# Module_MCU_ESP32Embed.net
KiCad netlist of a schematic drawn in EAGLE
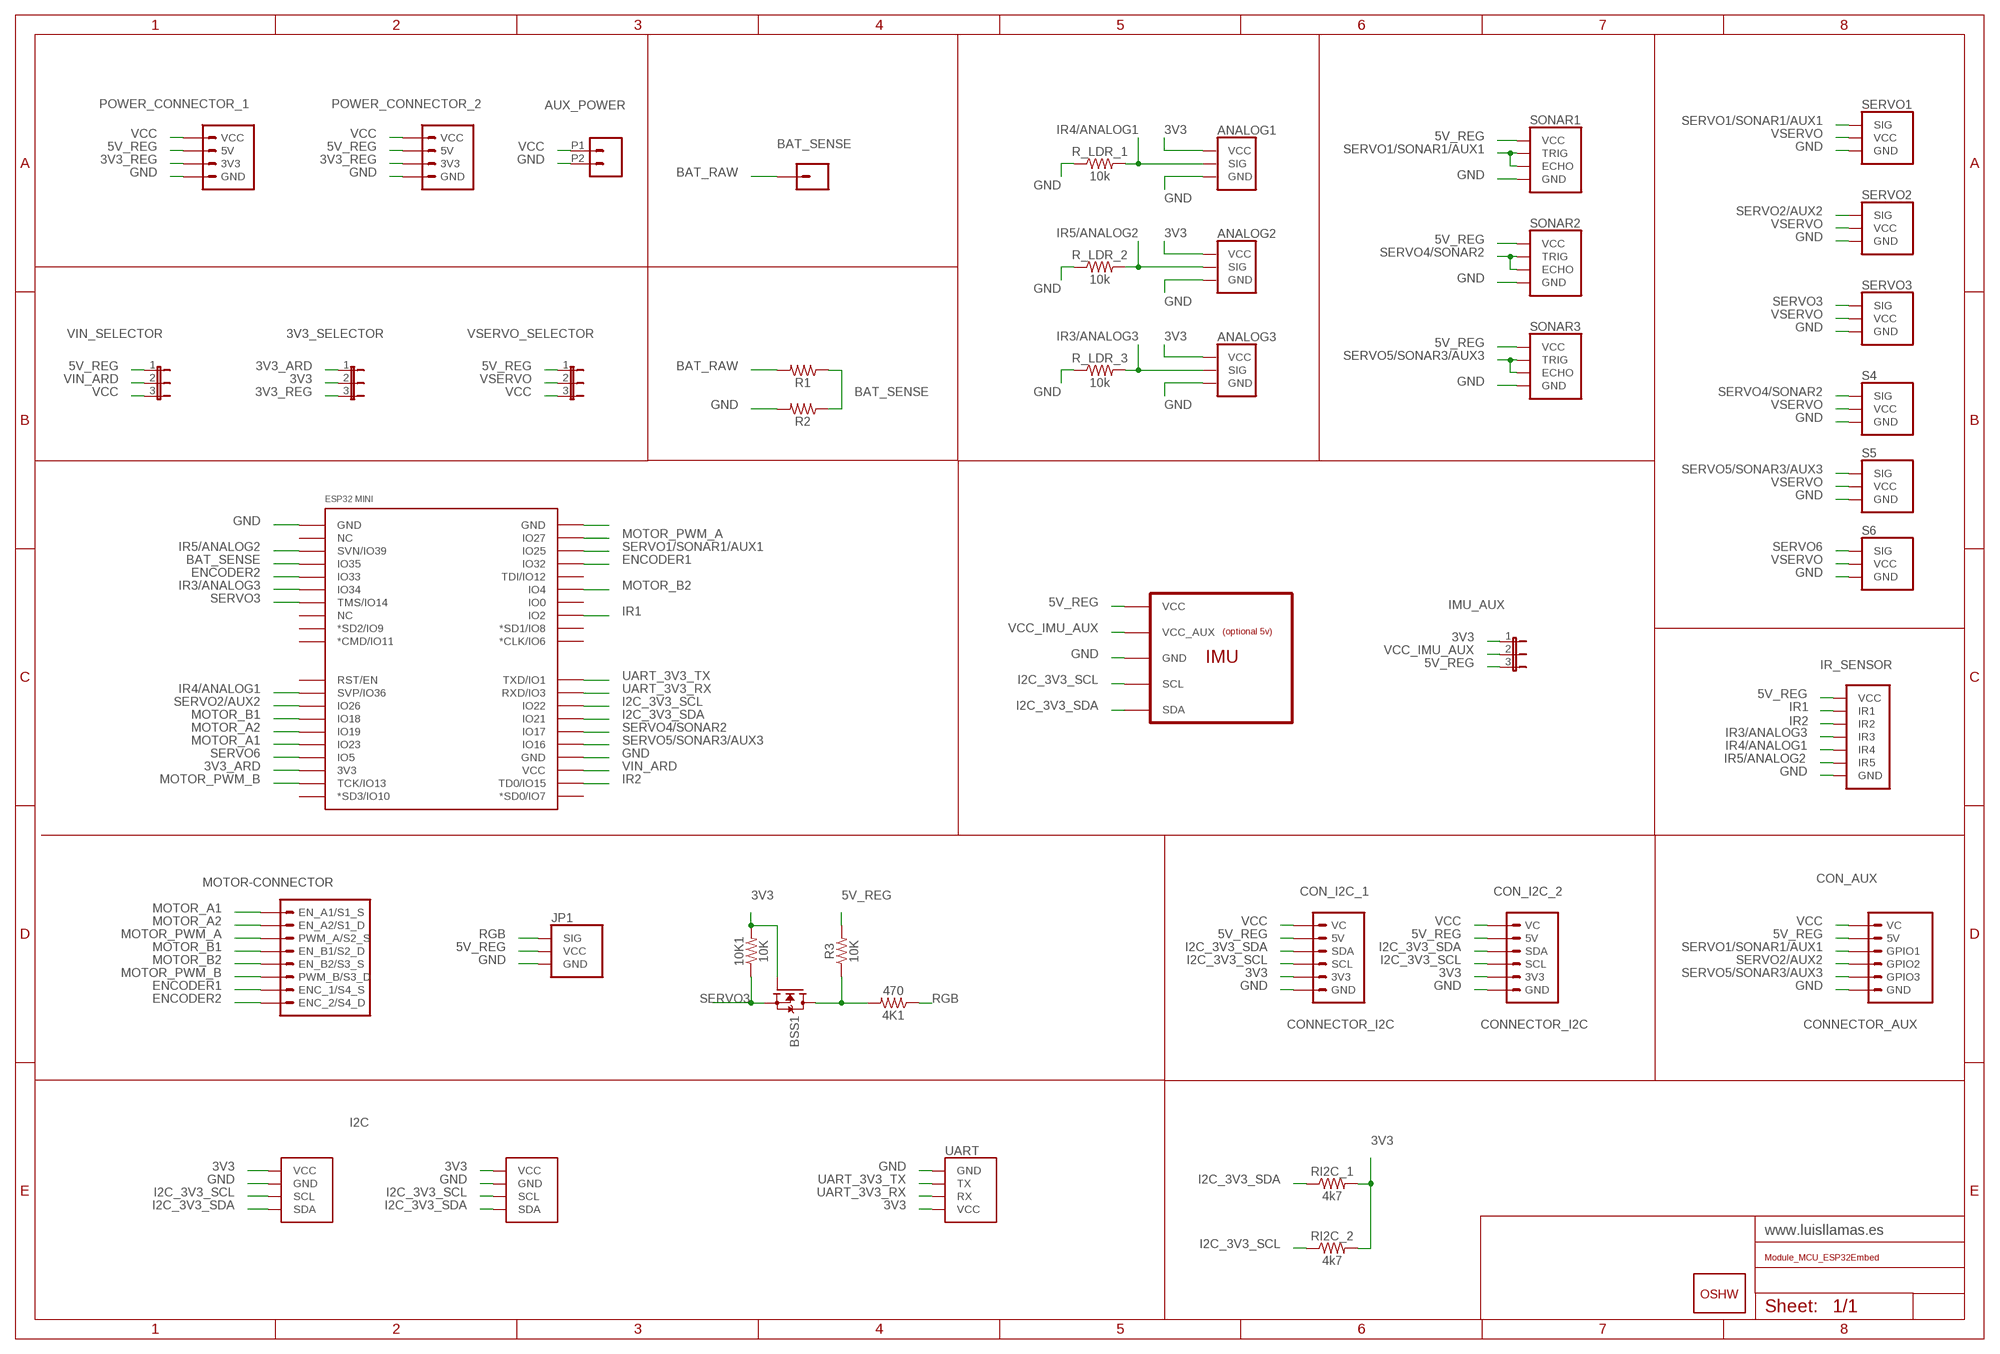
[diagram p0: schematic, sheet 1]

(export (version "E")
  (design (tool "Eeschema 10.0.6"))
  (components
    (comp (ref "3V3_SELECTOR")
      (value "JUMPER_3")
      (footprint "eagle-import:JUMPER_3")
      (libsource (lib "eagle-import") (part "JUMPER_3"))
    )
    (comp (ref "4K1")
      (value "470")
      (footprint "eagle-import:0805")
      (libsource (lib "eagle-import") (part "RESISTOR0805"))
    )
    (comp (ref "10K1")
      (value "10K")
      (footprint "eagle-import:0805")
      (libsource (lib "eagle-import") (part "RESISTOR0805"))
    )
    (comp (ref "ANALOG1")
      (value "LDR/OCT")
      (footprint "eagle-import:LDR")
      (libsource (lib "eagle-import") (part "LDR/OCT"))
    )
    (comp (ref "ANALOG2")
      (value "LDR/OCT")
      (footprint "eagle-import:LDR")
      (libsource (lib "eagle-import") (part "LDR/OCT"))
    )
    (comp (ref "ANALOG3")
      (value "LDR/OCT")
      (footprint "eagle-import:LDR")
      (libsource (lib "eagle-import") (part "LDR/OCT"))
    )
    (comp (ref "AUX_POWER")
      (value "CONN_022.54MM_SCREWTERM")
      (footprint "eagle-import:1X02_2.54_SCREWTERM")
      (libsource (lib "eagle-import") (part "CONN_022.54MM_SCREWTERM"))
    )
    (comp (ref "BAT_SENSE")
      (value "CONN_01")
      (footprint "eagle-import:1X01")
      (libsource (lib "eagle-import") (part "CONN_01"))
    )
    (comp (ref "BSS1")
      (value "MOSFET-N-SOT23")
      (footprint "eagle-import:SOT23")
      (libsource (lib "eagle-import") (part "MOSFET-N-SOT23"))
    )
    (comp (ref "CON_AUX")
      (value "CONNECTOR_AUX")
      (footprint "eagle-import:CONNECTOR_AUX")
      (libsource (lib "eagle-import") (part "CONNECTOR_AUX"))
    )
    (comp (ref "CON_I2C_1")
      (value "CONNECTOR_I2C")
      (footprint "eagle-import:CONNECTOR_I2C")
      (libsource (lib "eagle-import") (part "CONNECTOR_I2C"))
    )
    (comp (ref "CON_I2C_2")
      (value "CONNECTOR_I2C")
      (footprint "eagle-import:CONNECTOR_I2C")
      (libsource (lib "eagle-import") (part "CONNECTOR_I2C"))
    )
    (comp (ref "GOLD_ORB_SM1")
      (value "OSHWLOGO_GOLD_ORB_MED")
      (footprint "eagle-import:OSHW1")
      (libsource (lib "eagle-import") (part "OSHWLOGO_GOLD_ORB_MED"))
    )
    (comp (ref "I2C_1")
      (value "I2C")
      (footprint "eagle-import:I2C_VCC_GND_SCL_SDA")
      (libsource (lib "eagle-import") (part "GENERIC_I2CVCC_GND_SCL_SDA"))
    )
    (comp (ref "I2C_2")
      (value "GENERIC_I2CVCC_GND_SCL_SDA")
      (footprint "eagle-import:I2C_VCC_GND_SCL_SDA")
      (libsource (lib "eagle-import") (part "GENERIC_I2CVCC_GND_SCL_SDA"))
    )
    (comp (ref "IMU_AUX")
      (value "JUMPER_3")
      (footprint "eagle-import:JUMPER_3")
      (libsource (lib "eagle-import") (part "JUMPER_3"))
    )
    (comp (ref "IR_SENSOR")
      (value "IR-5/OCT")
      (footprint "eagle-import:IR-5")
      (libsource (lib "eagle-import") (part "IR-5/OCT"))
    )
    (comp (ref "JP1")
      (value "SERVOSERVO")
      (footprint "eagle-import:SERVO")
      (libsource (lib "eagle-import") (part "SERVOSERVO"))
    )
    (comp (ref "MOTOR_CONNECTOR")
      (value "MOTOR-CONNECTOR")
      (footprint "eagle-import:MOTOR-CONNECTOR")
      (libsource (lib "eagle-import") (part "MOTOR-CONNECTOR"))
    )
    (comp (ref "POWER_CONNECTOR_1")
      (value "POWER-CONNECTOR")
      (footprint "eagle-import:POWER-CONNECTOR")
      (libsource (lib "eagle-import") (part "POWER-CONNECTOR"))
    )
    (comp (ref "POWER_CONNECTOR_2")
      (value "POWER-CONNECTOR")
      (footprint "eagle-import:POWER-CONNECTOR")
      (libsource (lib "eagle-import") (part "POWER-CONNECTOR"))
    )
    (comp (ref "R1")
      (value "RESISTOR1206")
      (footprint "eagle-import:1206")
      (libsource (lib "eagle-import") (part "RESISTOR1206"))
    )
    (comp (ref "R2")
      (value "RESISTOR1206")
      (footprint "eagle-import:1206")
      (libsource (lib "eagle-import") (part "RESISTOR1206"))
    )
    (comp (ref "R3")
      (value "10K")
      (footprint "eagle-import:0805")
      (libsource (lib "eagle-import") (part "RESISTOR0805"))
    )
    (comp (ref "RI2C_1")
      (value "4k7")
      (footprint "eagle-import:1206")
      (libsource (lib "eagle-import") (part "RESISTOR1206"))
    )
    (comp (ref "RI2C_2")
      (value "4k7")
      (footprint "eagle-import:1206")
      (libsource (lib "eagle-import") (part "RESISTOR1206"))
    )
    (comp (ref "R_LDR_1")
      (value "10k")
      (footprint "eagle-import:1206")
      (libsource (lib "eagle-import") (part "RESISTOR1206"))
    )
    (comp (ref "R_LDR_2")
      (value "10k")
      (footprint "eagle-import:1206")
      (libsource (lib "eagle-import") (part "RESISTOR1206"))
    )
    (comp (ref "R_LDR_3")
      (value "10k")
      (footprint "eagle-import:1206")
      (libsource (lib "eagle-import") (part "RESISTOR1206"))
    )
    (comp (ref "S4")
      (value "SERVOSERVO")
      (footprint "eagle-import:SERVO")
      (libsource (lib "eagle-import") (part "SERVOSERVO"))
    )
    (comp (ref "S5")
      (value "SERVOSERVO")
      (footprint "eagle-import:SERVO")
      (libsource (lib "eagle-import") (part "SERVOSERVO"))
    )
    (comp (ref "S6")
      (value "SERVOSERVO")
      (footprint "eagle-import:SERVO")
      (libsource (lib "eagle-import") (part "SERVOSERVO"))
    )
    (comp (ref "SERVO1")
      (value "SERVOSERVO")
      (footprint "eagle-import:SERVO")
      (libsource (lib "eagle-import") (part "SERVOSERVO"))
    )
    (comp (ref "SERVO2")
      (value "SERVOSERVO")
      (footprint "eagle-import:SERVO")
      (libsource (lib "eagle-import") (part "SERVOSERVO"))
    )
    (comp (ref "SERVO3")
      (value "SERVOSERVO")
      (footprint "eagle-import:SERVO")
      (libsource (lib "eagle-import") (part "SERVOSERVO"))
    )
    (comp (ref "SONAR1")
      (value "ULTRASONIC/OCT")
      (footprint "eagle-import:ULTRASONIC")
      (libsource (lib "eagle-import") (part "ULTRASONIC/OCT"))
    )
    (comp (ref "SONAR2")
      (value "ULTRASONIC/OCT")
      (footprint "eagle-import:ULTRASONIC")
      (libsource (lib "eagle-import") (part "ULTRASONIC/OCT"))
    )
    (comp (ref "SONAR3")
      (value "ULTRASONIC/OCT")
      (footprint "eagle-import:ULTRASONIC")
      (libsource (lib "eagle-import") (part "ULTRASONIC/OCT"))
    )
    (comp (ref "U$5")
      (value "ESP32-WEMOS")
      (footprint "eagle-import:ESP32-WEMOS")
      (libsource (lib "eagle-import") (part "ESP32-WEMOS"))
    )
    (comp (ref "U1")
      (value "IMU_6/9/10DOFMPU6050")
      (footprint "eagle-import:IMU_6_9_10DOF")
      (libsource (lib "eagle-import") (part "IMU_6/9/10DOFMPU6050"))
    )
    (comp (ref "UART")
      (value "UART")
      (footprint "eagle-import:GENERIC_UART")
      (libsource (lib "eagle-import") (part "GENERIC_UARTGND_TX_RX_VCC"))
    )
    (comp (ref "VIN_SELECTOR")
      (value "JUMPER_3")
      (footprint "eagle-import:JUMPER_3")
      (libsource (lib "eagle-import") (part "JUMPER_3"))
    )
    (comp (ref "VSERVO_SELECTOR")
      (value "JUMPER_3")
      (footprint "eagle-import:JUMPER_3")
      (libsource (lib "eagle-import") (part "JUMPER_3"))
    )
  )
  (nets
    (net (code "1") (name "/3V3") (class "Default")
      (node (ref "10K1") (pin "2") (pinfunction "2_2") (pintype "passive"))
      (node (ref "3V3_SELECTOR") (pin "2") (pinfunction "2_2") (pintype "passive"))
      (node (ref "ANALOG1") (pin "VCC") (pinfunction "VCC_VCC") (pintype "power_in"))
      (node (ref "ANALOG2") (pin "VCC") (pinfunction "VCC_VCC") (pintype "power_in"))
      (node (ref "ANALOG3") (pin "VCC") (pinfunction "VCC_VCC") (pintype "power_in"))
      (node (ref "BSS1") (pin "1") (pinfunction "G_1") (pintype "passive"))
      (node (ref "CON_I2C_1") (pin "3V3") (pinfunction "3V3_3V3") (pintype "passive"))
      (node (ref "CON_I2C_2") (pin "3V3") (pinfunction "3V3_3V3") (pintype "passive"))
      (node (ref "I2C_1") (pin "VCC") (pinfunction "VCC_VCC") (pintype "power_in"))
      (node (ref "I2C_2") (pin "VCC") (pinfunction "VCC_VCC") (pintype "power_in"))
      (node (ref "IMU_AUX") (pin "1") (pinfunction "1_1") (pintype "passive"))
      (node (ref "RI2C_1") (pin "2") (pinfunction "2_2") (pintype "passive"))
      (node (ref "RI2C_2") (pin "2") (pinfunction "2_2") (pintype "passive"))
      (node (ref "UART") (pin "VCC") (pinfunction "VCC_VCC") (pintype "bidirectional"))
    )
    (net (code "2") (name "/3V3_ARD") (class "Default")
      (node (ref "3V3_SELECTOR") (pin "1") (pinfunction "1_1") (pintype "passive"))
      (node (ref "U$5") (pin "3V3") (pinfunction "3V3_3V3") (pintype "bidirectional"))
    )
    (net (code "3") (name "/3V3_REG") (class "Default")
      (node (ref "3V3_SELECTOR") (pin "3") (pinfunction "3_3") (pintype "passive"))
      (node (ref "POWER_CONNECTOR_1") (pin "3V3") (pinfunction "3V3_3V3") (pintype "passive"))
      (node (ref "POWER_CONNECTOR_2") (pin "3V3") (pinfunction "3V3_3V3") (pintype "passive"))
    )
    (net (code "4") (name "/5V_REG") (class "Default")
      (node (ref "CON_AUX") (pin "5V") (pinfunction "5V_5V") (pintype "passive"))
      (node (ref "CON_I2C_1") (pin "5V") (pinfunction "5V_5V") (pintype "passive"))
      (node (ref "CON_I2C_2") (pin "5V") (pinfunction "5V_5V") (pintype "passive"))
      (node (ref "IMU_AUX") (pin "3") (pinfunction "3_3") (pintype "passive"))
      (node (ref "IR_SENSOR") (pin "VCC") (pinfunction "VCC_VCC") (pintype "power_in"))
      (node (ref "JP1") (pin "VCC") (pinfunction "VCC_VCC") (pintype "power_in"))
      (node (ref "POWER_CONNECTOR_1") (pin "5V") (pinfunction "5V_5V") (pintype "passive"))
      (node (ref "POWER_CONNECTOR_2") (pin "5V") (pinfunction "5V_5V") (pintype "passive"))
      (node (ref "R3") (pin "2") (pinfunction "2_2") (pintype "passive"))
      (node (ref "SONAR1") (pin "VCC") (pinfunction "VCC_VCC") (pintype "power_in"))
      (node (ref "SONAR2") (pin "VCC") (pinfunction "VCC_VCC") (pintype "power_in"))
      (node (ref "SONAR3") (pin "VCC") (pinfunction "VCC_VCC") (pintype "power_in"))
      (node (ref "U1") (pin "VCC") (pinfunction "VCC_VCC") (pintype "power_in"))
      (node (ref "VIN_SELECTOR") (pin "1") (pinfunction "1_1") (pintype "passive"))
      (node (ref "VSERVO_SELECTOR") (pin "1") (pinfunction "1_1") (pintype "passive"))
    )
    (net (code "5") (name "/BAT_RAW") (class "Default")
      (node (ref "BAT_SENSE") (pin "1") (pinfunction "1_1") (pintype "passive"))
      (node (ref "R1") (pin "2") (pinfunction "2_2") (pintype "passive"))
    )
    (net (code "6") (name "/BAT_SENSE") (class "Default")
      (node (ref "R1") (pin "1") (pinfunction "1_1") (pintype "passive"))
      (node (ref "R2") (pin "1") (pinfunction "1_1") (pintype "passive"))
      (node (ref "U$5") (pin "IO35") (pinfunction "IO35_IO35") (pintype "bidirectional"))
    )
    (net (code "7") (name "/ENCODER1") (class "Default")
      (node (ref "MOTOR_CONNECTOR") (pin "ENC_1/S4_S") (pinfunction "ENC_1/S4_S_ENC_1/S4_S") (pintype "passive"))
      (node (ref "U$5") (pin "IO32") (pinfunction "IO32_IO32") (pintype "bidirectional"))
    )
    (net (code "8") (name "/ENCODER2") (class "Default")
      (node (ref "MOTOR_CONNECTOR") (pin "ENC_2/S4_D") (pinfunction "ENC_2/S4_D_ENC_2/S4_D") (pintype "passive"))
      (node (ref "U$5") (pin "IO33") (pinfunction "IO33_IO33") (pintype "bidirectional"))
    )
    (net (code "9") (name "/GND") (class "Default")
      (node (ref "ANALOG1") (pin "GND") (pinfunction "GND_GND") (pintype "power_in"))
      (node (ref "ANALOG2") (pin "GND") (pinfunction "GND_GND") (pintype "power_in"))
      (node (ref "ANALOG3") (pin "GND") (pinfunction "GND_GND") (pintype "power_in"))
      (node (ref "AUX_POWER") (pin "P2") (pinfunction "2_P2") (pintype "passive"))
      (node (ref "CON_AUX") (pin "GND") (pinfunction "GND_GND") (pintype "passive"))
      (node (ref "CON_I2C_1") (pin "GND") (pinfunction "GND_GND") (pintype "passive"))
      (node (ref "CON_I2C_2") (pin "GND") (pinfunction "GND_GND") (pintype "passive"))
      (node (ref "I2C_1") (pin "GND") (pinfunction "GND_GND") (pintype "power_in"))
      (node (ref "I2C_2") (pin "GND") (pinfunction "GND_GND") (pintype "power_in"))
      (node (ref "IR_SENSOR") (pin "GND") (pinfunction "GND_GND") (pintype "power_in"))
      (node (ref "JP1") (pin "GND") (pinfunction "GND_GND") (pintype "power_in"))
      (node (ref "POWER_CONNECTOR_1") (pin "GND") (pinfunction "GND_GND") (pintype "passive"))
      (node (ref "POWER_CONNECTOR_2") (pin "GND") (pinfunction "GND_GND") (pintype "passive"))
      (node (ref "R2") (pin "2") (pinfunction "2_2") (pintype "passive"))
      (node (ref "R_LDR_1") (pin "1") (pinfunction "1_1") (pintype "passive"))
      (node (ref "R_LDR_2") (pin "1") (pinfunction "1_1") (pintype "passive"))
      (node (ref "R_LDR_3") (pin "1") (pinfunction "1_1") (pintype "passive"))
      (node (ref "S4") (pin "GND") (pinfunction "GND_GND") (pintype "power_in"))
      (node (ref "S5") (pin "GND") (pinfunction "GND_GND") (pintype "power_in"))
      (node (ref "S6") (pin "GND") (pinfunction "GND_GND") (pintype "power_in"))
      (node (ref "SERVO1") (pin "GND") (pinfunction "GND_GND") (pintype "power_in"))
      (node (ref "SERVO2") (pin "GND") (pinfunction "GND_GND") (pintype "power_in"))
      (node (ref "SERVO3") (pin "GND") (pinfunction "GND_GND") (pintype "power_in"))
      (node (ref "SONAR1") (pin "GND") (pinfunction "GND_GND") (pintype "power_in"))
      (node (ref "SONAR2") (pin "GND") (pinfunction "GND_GND") (pintype "power_in"))
      (node (ref "SONAR3") (pin "GND") (pinfunction "GND_GND") (pintype "power_in"))
      (node (ref "U$5") (pin "GND@1") (pinfunction "GND_GND@1") (pintype "bidirectional"))
      (node (ref "U$5") (pin "GND@3") (pinfunction "GND_GND@3") (pintype "bidirectional"))
      (node (ref "U1") (pin "GND") (pinfunction "GND_GND") (pintype "power_in"))
      (node (ref "UART") (pin "GND") (pinfunction "GND_GND") (pintype "power_in"))
    )
    (net (code "10") (name "/I2C_3V3_SCL") (class "Default")
      (node (ref "CON_I2C_1") (pin "SCL") (pinfunction "SCL_SCL") (pintype "passive"))
      (node (ref "CON_I2C_2") (pin "SCL") (pinfunction "SCL_SCL") (pintype "passive"))
      (node (ref "I2C_1") (pin "SCL") (pinfunction "SCL_SCL") (pintype "bidirectional"))
      (node (ref "I2C_2") (pin "SCL") (pinfunction "SCL_SCL") (pintype "bidirectional"))
      (node (ref "RI2C_2") (pin "1") (pinfunction "1_1") (pintype "passive"))
      (node (ref "U$5") (pin "IO22") (pinfunction "IO22_IO22") (pintype "bidirectional"))
      (node (ref "U1") (pin "SCL") (pinfunction "SCL_SCL") (pintype "bidirectional"))
    )
    (net (code "11") (name "/I2C_3V3_SDA") (class "Default")
      (node (ref "CON_I2C_1") (pin "SDA") (pinfunction "SDA_SDA") (pintype "passive"))
      (node (ref "CON_I2C_2") (pin "SDA") (pinfunction "SDA_SDA") (pintype "passive"))
      (node (ref "I2C_1") (pin "SDA") (pinfunction "SDA_SDA") (pintype "bidirectional"))
      (node (ref "I2C_2") (pin "SDA") (pinfunction "SDA_SDA") (pintype "bidirectional"))
      (node (ref "RI2C_1") (pin "1") (pinfunction "1_1") (pintype "passive"))
      (node (ref "U$5") (pin "IO21") (pinfunction "IO21_IO21") (pintype "bidirectional"))
      (node (ref "U1") (pin "SDA") (pinfunction "SDA_SDA") (pintype "bidirectional"))
    )
    (net (code "12") (name "/IR1") (class "Default")
      (node (ref "IR_SENSOR") (pin "1") (pinfunction "IR1_1") (pintype "bidirectional"))
      (node (ref "U$5") (pin "IO2") (pinfunction "IO2_IO2") (pintype "bidirectional"))
    )
    (net (code "13") (name "/IR2") (class "Default")
      (node (ref "IR_SENSOR") (pin "2") (pinfunction "IR2_2") (pintype "bidirectional"))
      (node (ref "U$5") (pin "TD0/IO15") (pinfunction "TD0/IO15_TD0/IO15") (pintype "bidirectional"))
    )
    (net (code "14") (name "/IR3{slash}ANALOG3") (class "Default")
      (node (ref "ANALOG3") (pin "SIG") (pinfunction "SIG_SIG") (pintype "bidirectional"))
      (node (ref "IR_SENSOR") (pin "3") (pinfunction "IR3_3") (pintype "bidirectional"))
      (node (ref "R_LDR_3") (pin "2") (pinfunction "2_2") (pintype "passive"))
      (node (ref "U$5") (pin "IO34") (pinfunction "IO34_IO34") (pintype "bidirectional"))
    )
    (net (code "15") (name "/IR4{slash}ANALOG1") (class "Default")
      (node (ref "ANALOG1") (pin "SIG") (pinfunction "SIG_SIG") (pintype "bidirectional"))
      (node (ref "IR_SENSOR") (pin "4") (pinfunction "IR4_4") (pintype "bidirectional"))
      (node (ref "R_LDR_1") (pin "2") (pinfunction "2_2") (pintype "passive"))
      (node (ref "U$5") (pin "SVP/IO36") (pinfunction "SVP/IO36_SVP/IO36") (pintype "bidirectional"))
    )
    (net (code "16") (name "/IR5{slash}ANALOG2") (class "Default")
      (node (ref "ANALOG2") (pin "SIG") (pinfunction "SIG_SIG") (pintype "bidirectional"))
      (node (ref "IR_SENSOR") (pin "5") (pinfunction "IR5_5") (pintype "bidirectional"))
      (node (ref "R_LDR_2") (pin "2") (pinfunction "2_2") (pintype "passive"))
      (node (ref "U$5") (pin "SVN/IO39") (pinfunction "SVN/IO39_SVN/IO39") (pintype "bidirectional"))
    )
    (net (code "17") (name "/MOTOR_A1") (class "Default")
      (node (ref "MOTOR_CONNECTOR") (pin "EN_A1/S1_S") (pinfunction "EN_A1/S1_S_EN_A1/S1_S") (pintype "passive"))
      (node (ref "U$5") (pin "IO23") (pinfunction "IO23_IO23") (pintype "bidirectional"))
    )
    (net (code "18") (name "/MOTOR_A2") (class "Default")
      (node (ref "MOTOR_CONNECTOR") (pin "EN_A2/S1_D") (pinfunction "EN_A2/S1_D_EN_A2/S1_D") (pintype "passive"))
      (node (ref "U$5") (pin "IO19") (pinfunction "IO19_IO19") (pintype "bidirectional"))
    )
    (net (code "19") (name "/MOTOR_B1") (class "Default")
      (node (ref "MOTOR_CONNECTOR") (pin "EN_B1/S2_D") (pinfunction "EN_B1/S2_D_EN_B1/S2_D") (pintype "passive"))
      (node (ref "U$5") (pin "IO18") (pinfunction "IO18_IO18") (pintype "bidirectional"))
    )
    (net (code "20") (name "/MOTOR_B2") (class "Default")
      (node (ref "MOTOR_CONNECTOR") (pin "EN_B2/S3_S") (pinfunction "EN_B2/S3_S_EN_B2/S3_S") (pintype "passive"))
      (node (ref "U$5") (pin "IO4") (pinfunction "IO4_IO4") (pintype "bidirectional"))
    )
    (net (code "21") (name "/MOTOR_PWM_A") (class "Default")
      (node (ref "MOTOR_CONNECTOR") (pin "PWM_A/S2_S") (pinfunction "PWM_A/S2_S_PWM_A/S2_S") (pintype "passive"))
      (node (ref "U$5") (pin "IO27") (pinfunction "IO27_IO27") (pintype "bidirectional"))
    )
    (net (code "22") (name "/MOTOR_PWM_B") (class "Default")
      (node (ref "MOTOR_CONNECTOR") (pin "PWM_B/S3_D") (pinfunction "PWM_B/S3_D_PWM_B/S3_D") (pintype "passive"))
      (node (ref "U$5") (pin "TCK/IO13") (pinfunction "TCK/IO13_TCK/IO13") (pintype "bidirectional"))
    )
    (net (code "23") (name "/RGB") (class "Default")
      (node (ref "4K1") (pin "1") (pinfunction "1_1") (pintype "passive"))
      (node (ref "JP1") (pin "SIG") (pinfunction "SIG_SIG") (pintype "bidirectional"))
    )
    (net (code "24") (name "/SERVO1{slash}SONAR1{slash}AUX1") (class "Default")
      (node (ref "CON_AUX") (pin "GPIO1") (pinfunction "GPIO1_GPIO1") (pintype "passive"))
      (node (ref "SERVO1") (pin "SIG") (pinfunction "SIG_SIG") (pintype "bidirectional"))
      (node (ref "SONAR1") (pin "ECHO") (pinfunction "ECHO_ECHO") (pintype "bidirectional"))
      (node (ref "SONAR1") (pin "TRIG") (pinfunction "TRIG_TRIG") (pintype "bidirectional"))
      (node (ref "U$5") (pin "IO25") (pinfunction "IO25_IO25") (pintype "bidirectional"))
    )
    (net (code "25") (name "/SERVO2{slash}AUX2") (class "Default")
      (node (ref "CON_AUX") (pin "GPIO2") (pinfunction "GPIO2_GPIO2") (pintype "passive"))
      (node (ref "SERVO2") (pin "SIG") (pinfunction "SIG_SIG") (pintype "bidirectional"))
      (node (ref "U$5") (pin "IO26") (pinfunction "IO26_IO26") (pintype "bidirectional"))
    )
    (net (code "26") (name "/SERVO3") (class "Default")
      (node (ref "10K1") (pin "1") (pinfunction "1_1") (pintype "passive"))
      (node (ref "BSS1") (pin "2") (pinfunction "S_2") (pintype "passive"))
      (node (ref "SERVO3") (pin "SIG") (pinfunction "SIG_SIG") (pintype "bidirectional"))
      (node (ref "U$5") (pin "TMS/IO14") (pinfunction "TMS/IO14_TMS/IO14") (pintype "bidirectional"))
    )
    (net (code "27") (name "/SERVO4{slash}SONAR2") (class "Default")
      (node (ref "S4") (pin "SIG") (pinfunction "SIG_SIG") (pintype "bidirectional"))
      (node (ref "SONAR2") (pin "ECHO") (pinfunction "ECHO_ECHO") (pintype "bidirectional"))
      (node (ref "SONAR2") (pin "TRIG") (pinfunction "TRIG_TRIG") (pintype "bidirectional"))
      (node (ref "U$5") (pin "IO17") (pinfunction "IO17_IO17") (pintype "bidirectional"))
    )
    (net (code "28") (name "/SERVO5{slash}SONAR3{slash}AUX3") (class "Default")
      (node (ref "CON_AUX") (pin "GPIO3") (pinfunction "GPIO3_GPIO3") (pintype "passive"))
      (node (ref "S5") (pin "SIG") (pinfunction "SIG_SIG") (pintype "bidirectional"))
      (node (ref "SONAR3") (pin "ECHO") (pinfunction "ECHO_ECHO") (pintype "bidirectional"))
      (node (ref "SONAR3") (pin "TRIG") (pinfunction "TRIG_TRIG") (pintype "bidirectional"))
      (node (ref "U$5") (pin "IO16") (pinfunction "IO16_IO16") (pintype "bidirectional"))
    )
    (net (code "29") (name "/SERVO6") (class "Default")
      (node (ref "S6") (pin "SIG") (pinfunction "SIG_SIG") (pintype "bidirectional"))
      (node (ref "U$5") (pin "IO5") (pinfunction "IO5_IO5") (pintype "bidirectional"))
    )
    (net (code "30") (name "/UART_3V3_RX") (class "Default")
      (node (ref "U$5") (pin "RXD/IO3") (pinfunction "RXD/IO3_RXD/IO3") (pintype "bidirectional"))
      (node (ref "UART") (pin "RX") (pinfunction "RX_RX") (pintype "bidirectional"))
    )
    (net (code "31") (name "/UART_3V3_TX") (class "Default")
      (node (ref "U$5") (pin "TXD/IO1") (pinfunction "TXD/IO1_TXD/IO1") (pintype "bidirectional"))
      (node (ref "UART") (pin "TX") (pinfunction "TX_TX") (pintype "power_in"))
    )
    (net (code "32") (name "/VCC") (class "Default")
      (node (ref "AUX_POWER") (pin "P1") (pinfunction "1_P1") (pintype "passive"))
      (node (ref "CON_AUX") (pin "VC") (pinfunction "VC_VC") (pintype "passive"))
      (node (ref "CON_I2C_1") (pin "VC") (pinfunction "VC_VC") (pintype "passive"))
      (node (ref "CON_I2C_2") (pin "VC") (pinfunction "VC_VC") (pintype "passive"))
      (node (ref "POWER_CONNECTOR_1") (pin "VCC") (pinfunction "VCC_VCC") (pintype "passive"))
      (node (ref "POWER_CONNECTOR_2") (pin "VCC") (pinfunction "VCC_VCC") (pintype "passive"))
      (node (ref "VIN_SELECTOR") (pin "3") (pinfunction "3_3") (pintype "passive"))
      (node (ref "VSERVO_SELECTOR") (pin "3") (pinfunction "3_3") (pintype "passive"))
    )
    (net (code "33") (name "/VCC_IMU_AUX") (class "Default")
      (node (ref "IMU_AUX") (pin "2") (pinfunction "2_2") (pintype "passive"))
      (node (ref "U1") (pin "VCC_AUX") (pinfunction "VCC_AUX_VCC_AUX") (pintype "power_in"))
    )
    (net (code "34") (name "/VIN_ARD") (class "Default")
      (node (ref "U$5") (pin "VCC") (pinfunction "VCC_VCC") (pintype "bidirectional"))
      (node (ref "VIN_SELECTOR") (pin "2") (pinfunction "2_2") (pintype "passive"))
    )
    (net (code "35") (name "/VSERVO") (class "Default")
      (node (ref "S4") (pin "VCC") (pinfunction "VCC_VCC") (pintype "power_in"))
      (node (ref "S5") (pin "VCC") (pinfunction "VCC_VCC") (pintype "power_in"))
      (node (ref "S6") (pin "VCC") (pinfunction "VCC_VCC") (pintype "power_in"))
      (node (ref "SERVO1") (pin "VCC") (pinfunction "VCC_VCC") (pintype "power_in"))
      (node (ref "SERVO2") (pin "VCC") (pinfunction "VCC_VCC") (pintype "power_in"))
      (node (ref "SERVO3") (pin "VCC") (pinfunction "VCC_VCC") (pintype "power_in"))
      (node (ref "VSERVO_SELECTOR") (pin "2") (pinfunction "2_2") (pintype "passive"))
    )
    (net (code "36") (name "Net-(BSS1-D)") (class "Default")
      (node (ref "4K1") (pin "2") (pinfunction "2_2") (pintype "passive"))
      (node (ref "BSS1") (pin "3") (pinfunction "D_3") (pintype "passive"))
      (node (ref "R3") (pin "1") (pinfunction "1_1") (pintype "passive"))
    )
    (net (code "37") (name "unconnected-(U$5-*CLK{slash}IO6-PadCLK{slash}IO6)") (class "Default")
      (node (ref "U$5") (pin "CLK/IO6") (pinfunction "*CLK/IO6_CLK/IO6") (pintype "bidirectional"))
    )
    (net (code "38") (name "unconnected-(U$5-*CMD{slash}IO11-PadCMD{slash}IO11)") (class "Default")
      (node (ref "U$5") (pin "CMD/IO11") (pinfunction "*CMD/IO11_CMD/IO11") (pintype "bidirectional"))
    )
    (net (code "39") (name "unconnected-(U$5-*SD0{slash}IO7-PadSD0{slash}IO7)") (class "Default")
      (node (ref "U$5") (pin "SD0/IO7") (pinfunction "*SD0/IO7_SD0/IO7") (pintype "bidirectional"))
    )
    (net (code "40") (name "unconnected-(U$5-*SD1{slash}IO8-PadSD1{slash}IO8)") (class "Default")
      (node (ref "U$5") (pin "SD1/IO8") (pinfunction "*SD1/IO8_SD1/IO8") (pintype "bidirectional"))
    )
    (net (code "41") (name "unconnected-(U$5-*SD2{slash}IO9-PadSD2{slash}IO9)") (class "Default")
      (node (ref "U$5") (pin "SD2/IO9") (pinfunction "*SD2/IO9_SD2/IO9") (pintype "bidirectional"))
    )
    (net (code "42") (name "unconnected-(U$5-*SD3{slash}IO10-PadSD3{slash}IO10)") (class "Default")
      (node (ref "U$5") (pin "SD3/IO10") (pinfunction "*SD3/IO10_SD3/IO10") (pintype "bidirectional"))
    )
    (net (code "43") (name "unconnected-(U$5-GND-PadGND@2)") (class "Default")
      (node (ref "U$5") (pin "GND@2") (pinfunction "GND_GND@2") (pintype "bidirectional"))
    )
    (net (code "44") (name "unconnected-(U$5-NC-PadNC@1)") (class "Default")
      (node (ref "U$5") (pin "NC@1") (pinfunction "NC_NC@1") (pintype "bidirectional"))
    )
    (net (code "45") (name "unconnected-(U$5-NC-PadNC@2)") (class "Default")
      (node (ref "U$5") (pin "NC@2") (pinfunction "NC_NC@2") (pintype "bidirectional"))
    )
    (net (code "46") (name "unconnected-(U$5-PadIO0)") (class "Default")
      (node (ref "U$5") (pin "IO0") (pinfunction "IO0_IO0") (pintype "bidirectional"))
    )
    (net (code "47") (name "unconnected-(U$5-PadRST{slash}EN)") (class "Default")
      (node (ref "U$5") (pin "RST/EN") (pinfunction "RST/EN_RST/EN") (pintype "bidirectional"))
    )
    (net (code "48") (name "unconnected-(U$5-PadTDI{slash}IO12)") (class "Default")
      (node (ref "U$5") (pin "TDI/IO12") (pinfunction "TDI/IO12_TDI/IO12") (pintype "bidirectional"))
    )
  )
)
